# PanneauLed.net
KiCad netlist of a schematic drawn in Altium Designer
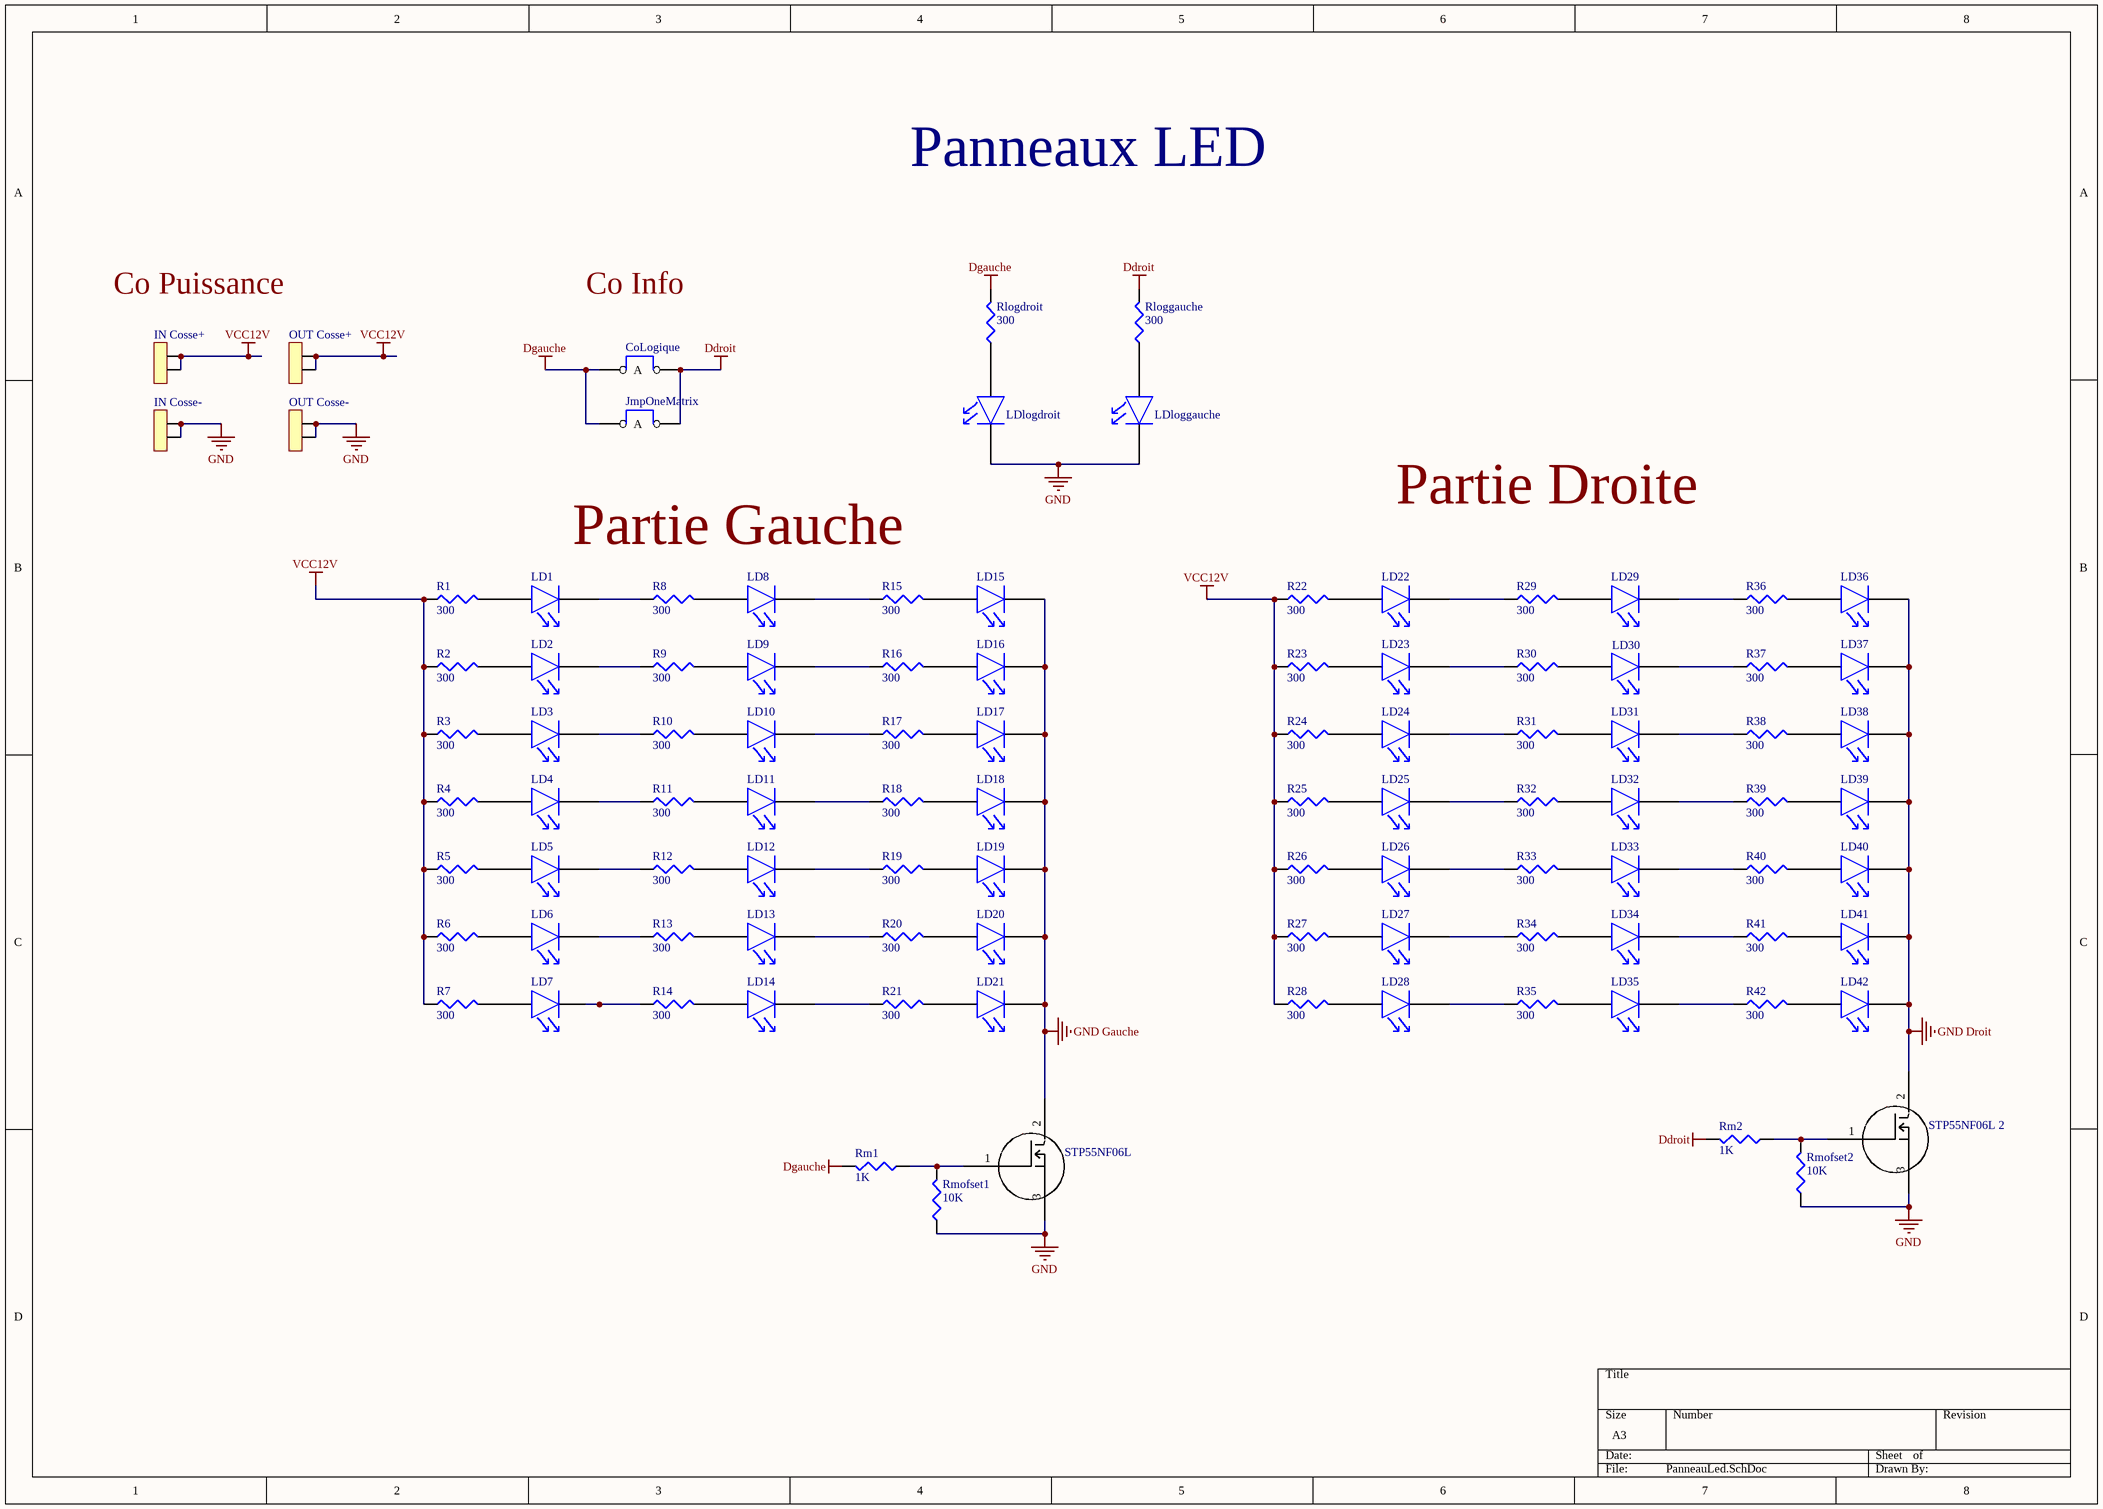
[diagram p0: PanneauLed.SchDoc]

(export (version "E")
  (design (tool "Eeschema 10.0.6"))
  (components
    (comp (ref "CoLogique")
      (value "JUMPER2")
      (footprint "JMP2-100")
      (description "cavalier 1 position")
      (libsource (lib "ISEN_basics") (part "JUMPER2"))
    )
    (comp (ref "IN Cosse+")
      (value "comment")
      (footprint "POWER2")
      (description "connecteur alim 2 pôles")
      (libsource (lib "ISEN_basics") (part "POWER2"))
    )
    (comp (ref "IN Cosse-")
      (value "comment")
      (footprint "POWER2")
      (description "connecteur alim 2 pôles")
      (libsource (lib "ISEN_basics") (part "POWER2"))
    )
    (comp (ref "JmpOneMatrix")
      (value "JUMPER2")
      (footprint "JMP2-100")
      (description "cavalier 1 position")
      (libsource (lib "ISEN_basics") (part "JUMPER2"))
    )
    (comp (ref "LD1")
      (value "comment")
      (footprint "LED1206")
      (description "LED 5mm/3mm/CMS")
      (libsource (lib "ISEN_basics") (part "LED"))
    )
    (comp (ref "LD2")
      (value "comment")
      (footprint "LED1206")
      (description "LED 5mm/3mm/CMS")
      (libsource (lib "ISEN_basics") (part "LED"))
    )
    (comp (ref "LD3")
      (value "comment")
      (footprint "LED1206")
      (description "LED 5mm/3mm/CMS")
      (libsource (lib "ISEN_basics") (part "LED"))
    )
    (comp (ref "LD4")
      (value "comment")
      (footprint "LED1206")
      (description "LED 5mm/3mm/CMS")
      (libsource (lib "ISEN_basics") (part "LED"))
    )
    (comp (ref "LD5")
      (value "comment")
      (footprint "LED1206")
      (description "LED 5mm/3mm/CMS")
      (libsource (lib "ISEN_basics") (part "LED"))
    )
    (comp (ref "LD6")
      (value "comment")
      (footprint "LED1206")
      (description "LED 5mm/3mm/CMS")
      (libsource (lib "ISEN_basics") (part "LED"))
    )
    (comp (ref "LD7")
      (value "comment")
      (footprint "LED1206")
      (description "LED 5mm/3mm/CMS")
      (libsource (lib "ISEN_basics") (part "LED"))
    )
    (comp (ref "LD8")
      (value "comment")
      (footprint "LED1206")
      (description "LED 5mm/3mm/CMS")
      (libsource (lib "ISEN_basics") (part "LED"))
    )
    (comp (ref "LD9")
      (value "comment")
      (footprint "LED1206")
      (description "LED 5mm/3mm/CMS")
      (libsource (lib "ISEN_basics") (part "LED"))
    )
    (comp (ref "LD10")
      (value "comment")
      (footprint "LED1206")
      (description "LED 5mm/3mm/CMS")
      (libsource (lib "ISEN_basics") (part "LED"))
    )
    (comp (ref "LD11")
      (value "comment")
      (footprint "LED1206")
      (description "LED 5mm/3mm/CMS")
      (libsource (lib "ISEN_basics") (part "LED"))
    )
    (comp (ref "LD12")
      (value "comment")
      (footprint "LED1206")
      (description "LED 5mm/3mm/CMS")
      (libsource (lib "ISEN_basics") (part "LED"))
    )
    (comp (ref "LD13")
      (value "comment")
      (footprint "LED1206")
      (description "LED 5mm/3mm/CMS")
      (libsource (lib "ISEN_basics") (part "LED"))
    )
    (comp (ref "LD14")
      (value "comment")
      (footprint "LED1206")
      (description "LED 5mm/3mm/CMS")
      (libsource (lib "ISEN_basics") (part "LED"))
    )
    (comp (ref "LD15")
      (value "comment")
      (footprint "LED1206")
      (description "LED 5mm/3mm/CMS")
      (libsource (lib "ISEN_basics") (part "LED"))
    )
    (comp (ref "LD16")
      (value "comment")
      (footprint "LED1206")
      (description "LED 5mm/3mm/CMS")
      (libsource (lib "ISEN_basics") (part "LED"))
    )
    (comp (ref "LD17")
      (value "comment")
      (footprint "LED1206")
      (description "LED 5mm/3mm/CMS")
      (libsource (lib "ISEN_basics") (part "LED"))
    )
    (comp (ref "LD18")
      (value "comment")
      (footprint "LED1206")
      (description "LED 5mm/3mm/CMS")
      (libsource (lib "ISEN_basics") (part "LED"))
    )
    (comp (ref "LD19")
      (value "comment")
      (footprint "LED1206")
      (description "LED 5mm/3mm/CMS")
      (libsource (lib "ISEN_basics") (part "LED"))
    )
    (comp (ref "LD20")
      (value "comment")
      (footprint "LED1206")
      (description "LED 5mm/3mm/CMS")
      (libsource (lib "ISEN_basics") (part "LED"))
    )
    (comp (ref "LD21")
      (value "comment")
      (footprint "LED1206")
      (description "LED 5mm/3mm/CMS")
      (libsource (lib "ISEN_basics") (part "LED"))
    )
    (comp (ref "LD22")
      (value "comment")
      (footprint "LED1206")
      (description "LED 5mm/3mm/CMS")
      (libsource (lib "ISEN_basics") (part "LED"))
    )
    (comp (ref "LD23")
      (value "comment")
      (footprint "LED1206")
      (description "LED 5mm/3mm/CMS")
      (libsource (lib "ISEN_basics") (part "LED"))
    )
    (comp (ref "LD24")
      (value "comment")
      (footprint "LED1206")
      (description "LED 5mm/3mm/CMS")
      (libsource (lib "ISEN_basics") (part "LED"))
    )
    (comp (ref "LD25")
      (value "comment")
      (footprint "LED1206")
      (description "LED 5mm/3mm/CMS")
      (libsource (lib "ISEN_basics") (part "LED"))
    )
    (comp (ref "LD26")
      (value "comment")
      (footprint "LED1206")
      (description "LED 5mm/3mm/CMS")
      (libsource (lib "ISEN_basics") (part "LED"))
    )
    (comp (ref "LD27")
      (value "comment")
      (footprint "LED1206")
      (description "LED 5mm/3mm/CMS")
      (libsource (lib "ISEN_basics") (part "LED"))
    )
    (comp (ref "LD28")
      (value "comment")
      (footprint "LED1206")
      (description "LED 5mm/3mm/CMS")
      (libsource (lib "ISEN_basics") (part "LED"))
    )
    (comp (ref "LD29")
      (value "comment")
      (footprint "LED1206")
      (description "LED 5mm/3mm/CMS")
      (libsource (lib "ISEN_basics") (part "LED"))
    )
    (comp (ref "LD30")
      (value "comment")
      (footprint "LED1206")
      (description "LED 5mm/3mm/CMS")
      (libsource (lib "ISEN_basics") (part "LED"))
    )
    (comp (ref "LD31")
      (value "comment")
      (footprint "LED1206")
      (description "LED 5mm/3mm/CMS")
      (libsource (lib "ISEN_basics") (part "LED"))
    )
    (comp (ref "LD32")
      (value "comment")
      (footprint "LED1206")
      (description "LED 5mm/3mm/CMS")
      (libsource (lib "ISEN_basics") (part "LED"))
    )
    (comp (ref "LD33")
      (value "comment")
      (footprint "LED1206")
      (description "LED 5mm/3mm/CMS")
      (libsource (lib "ISEN_basics") (part "LED"))
    )
    (comp (ref "LD34")
      (value "comment")
      (footprint "LED1206")
      (description "LED 5mm/3mm/CMS")
      (libsource (lib "ISEN_basics") (part "LED"))
    )
    (comp (ref "LD35")
      (value "comment")
      (footprint "LED1206")
      (description "LED 5mm/3mm/CMS")
      (libsource (lib "ISEN_basics") (part "LED"))
    )
    (comp (ref "LD36")
      (value "comment")
      (footprint "LED1206")
      (description "LED 5mm/3mm/CMS")
      (libsource (lib "ISEN_basics") (part "LED"))
    )
    (comp (ref "LD37")
      (value "comment")
      (footprint "LED1206")
      (description "LED 5mm/3mm/CMS")
      (libsource (lib "ISEN_basics") (part "LED"))
    )
    (comp (ref "LD38")
      (value "comment")
      (footprint "LED1206")
      (description "LED 5mm/3mm/CMS")
      (libsource (lib "ISEN_basics") (part "LED"))
    )
    (comp (ref "LD39")
      (value "comment")
      (footprint "LED1206")
      (description "LED 5mm/3mm/CMS")
      (libsource (lib "ISEN_basics") (part "LED"))
    )
    (comp (ref "LD40")
      (value "comment")
      (footprint "LED1206")
      (description "LED 5mm/3mm/CMS")
      (libsource (lib "ISEN_basics") (part "LED"))
    )
    (comp (ref "LD41")
      (value "comment")
      (footprint "LED1206")
      (description "LED 5mm/3mm/CMS")
      (libsource (lib "ISEN_basics") (part "LED"))
    )
    (comp (ref "LD42")
      (value "comment")
      (footprint "LED1206")
      (description "LED 5mm/3mm/CMS")
      (libsource (lib "ISEN_basics") (part "LED"))
    )
    (comp (ref "LDlogdroit")
      (value "comment")
      (footprint "LED1206")
      (description "LED 5mm/3mm/CMS")
      (libsource (lib "ISEN_basics") (part "LED"))
    )
    (comp (ref "LDloggauche")
      (value "comment")
      (footprint "LED1206")
      (description "LED 5mm/3mm/CMS")
      (libsource (lib "ISEN_basics") (part "LED"))
    )
    (comp (ref "OUT Cosse+")
      (value "~")
      (footprint "POWER2")
      (description "connecteur alim 2 pôles")
      (libsource (lib "ISEN_basics") (part "POWER2"))
    )
    (comp (ref "OUT Cosse-")
      (value "comment")
      (footprint "POWER2")
      (description "connecteur alim 2 pôles")
      (libsource (lib "ISEN_basics") (part "POWER2"))
    )
    (comp (ref "R1")
      (value "300")
      (footprint "0805")
      (description "resistance")
      (fields (field (name "Comment") "RES"))
      (libsource (lib "ISEN_basics") (part "RES"))
    )
    (comp (ref "R2")
      (value "300")
      (footprint "0805")
      (description "resistance")
      (fields (field (name "Comment") "RES"))
      (libsource (lib "ISEN_basics") (part "RES"))
    )
    (comp (ref "R3")
      (value "300")
      (footprint "0805")
      (description "resistance")
      (fields (field (name "Comment") "RES"))
      (libsource (lib "ISEN_basics") (part "RES"))
    )
    (comp (ref "R4")
      (value "300")
      (footprint "0805")
      (description "resistance")
      (fields (field (name "Comment") "RES"))
      (libsource (lib "ISEN_basics") (part "RES"))
    )
    (comp (ref "R5")
      (value "300")
      (footprint "0805")
      (description "resistance")
      (fields (field (name "Comment") "RES"))
      (libsource (lib "ISEN_basics") (part "RES"))
    )
    (comp (ref "R6")
      (value "300")
      (footprint "0805")
      (description "resistance")
      (fields (field (name "Comment") "RES"))
      (libsource (lib "ISEN_basics") (part "RES"))
    )
    (comp (ref "R7")
      (value "300")
      (footprint "0805")
      (description "resistance")
      (fields (field (name "Comment") "RES"))
      (libsource (lib "ISEN_basics") (part "RES"))
    )
    (comp (ref "R8")
      (value "300")
      (footprint "0805")
      (description "resistance")
      (fields (field (name "Comment") "RES"))
      (libsource (lib "ISEN_basics") (part "RES"))
    )
    (comp (ref "R9")
      (value "300")
      (footprint "0805")
      (description "resistance")
      (fields (field (name "Comment") "RES"))
      (libsource (lib "ISEN_basics") (part "RES"))
    )
    (comp (ref "R10")
      (value "300")
      (footprint "0805")
      (description "resistance")
      (fields (field (name "Comment") "RES"))
      (libsource (lib "ISEN_basics") (part "RES"))
    )
    (comp (ref "R11")
      (value "300")
      (footprint "0805")
      (description "resistance")
      (fields (field (name "Comment") "RES"))
      (libsource (lib "ISEN_basics") (part "RES"))
    )
    (comp (ref "R12")
      (value "300")
      (footprint "0805")
      (description "resistance")
      (fields (field (name "Comment") "RES"))
      (libsource (lib "ISEN_basics") (part "RES"))
    )
    (comp (ref "R13")
      (value "300")
      (footprint "0805")
      (description "resistance")
      (fields (field (name "Comment") "RES"))
      (libsource (lib "ISEN_basics") (part "RES"))
    )
    (comp (ref "R14")
      (value "300")
      (footprint "0805")
      (description "resistance")
      (fields (field (name "Comment") "RES"))
      (libsource (lib "ISEN_basics") (part "RES"))
    )
    (comp (ref "R15")
      (value "300")
      (footprint "0805")
      (description "resistance")
      (fields (field (name "Comment") "RES"))
      (libsource (lib "ISEN_basics") (part "RES"))
    )
    (comp (ref "R16")
      (value "300")
      (footprint "0805")
      (description "resistance")
      (fields (field (name "Comment") "RES"))
      (libsource (lib "ISEN_basics") (part "RES"))
    )
    (comp (ref "R17")
      (value "300")
      (footprint "0805")
      (description "resistance")
      (fields (field (name "Comment") "RES"))
      (libsource (lib "ISEN_basics") (part "RES"))
    )
    (comp (ref "R18")
      (value "300")
      (footprint "0805")
      (description "resistance")
      (fields (field (name "Comment") "RES"))
      (libsource (lib "ISEN_basics") (part "RES"))
    )
    (comp (ref "R19")
      (value "300")
      (footprint "0805")
      (description "resistance")
      (fields (field (name "Comment") "RES"))
      (libsource (lib "ISEN_basics") (part "RES"))
    )
    (comp (ref "R20")
      (value "300")
      (footprint "0805")
      (description "resistance")
      (fields (field (name "Comment") "RES"))
      (libsource (lib "ISEN_basics") (part "RES"))
    )
    (comp (ref "R21")
      (value "300")
      (footprint "0805")
      (description "resistance")
      (fields (field (name "Comment") "RES"))
      (libsource (lib "ISEN_basics") (part "RES"))
    )
    (comp (ref "R22")
      (value "300")
      (footprint "0805")
      (description "resistance")
      (fields (field (name "Comment") "RES"))
      (libsource (lib "ISEN_basics") (part "RES"))
    )
    (comp (ref "R23")
      (value "300")
      (footprint "0805")
      (description "resistance")
      (fields (field (name "Comment") "RES"))
      (libsource (lib "ISEN_basics") (part "RES"))
    )
    (comp (ref "R24")
      (value "300")
      (footprint "0805")
      (description "resistance")
      (fields (field (name "Comment") "RES"))
      (libsource (lib "ISEN_basics") (part "RES"))
    )
    (comp (ref "R25")
      (value "300")
      (footprint "0805")
      (description "resistance")
      (fields (field (name "Comment") "RES"))
      (libsource (lib "ISEN_basics") (part "RES"))
    )
    (comp (ref "R26")
      (value "300")
      (footprint "0805")
      (description "resistance")
      (fields (field (name "Comment") "RES"))
      (libsource (lib "ISEN_basics") (part "RES"))
    )
    (comp (ref "R27")
      (value "300")
      (footprint "0805")
      (description "resistance")
      (fields (field (name "Comment") "RES"))
      (libsource (lib "ISEN_basics") (part "RES"))
    )
    (comp (ref "R28")
      (value "300")
      (footprint "0805")
      (description "resistance")
      (fields (field (name "Comment") "RES"))
      (libsource (lib "ISEN_basics") (part "RES"))
    )
    (comp (ref "R29")
      (value "300")
      (footprint "0805")
      (description "resistance")
      (fields (field (name "Comment") "RES"))
      (libsource (lib "ISEN_basics") (part "RES"))
    )
    (comp (ref "R30")
      (value "300")
      (footprint "0805")
      (description "resistance")
      (fields (field (name "Comment") "RES"))
      (libsource (lib "ISEN_basics") (part "RES"))
    )
    (comp (ref "R31")
      (value "300")
      (footprint "0805")
      (description "resistance")
      (fields (field (name "Comment") "RES"))
      (libsource (lib "ISEN_basics") (part "RES"))
    )
    (comp (ref "R32")
      (value "300")
      (footprint "0805")
      (description "resistance")
      (fields (field (name "Comment") "RES"))
      (libsource (lib "ISEN_basics") (part "RES"))
    )
    (comp (ref "R33")
      (value "300")
      (footprint "0805")
      (description "resistance")
      (fields (field (name "Comment") "RES"))
      (libsource (lib "ISEN_basics") (part "RES"))
    )
    (comp (ref "R34")
      (value "300")
      (footprint "0805")
      (description "resistance")
      (fields (field (name "Comment") "RES"))
      (libsource (lib "ISEN_basics") (part "RES"))
    )
    (comp (ref "R35")
      (value "300")
      (footprint "0805")
      (description "resistance")
      (fields (field (name "Comment") "RES"))
      (libsource (lib "ISEN_basics") (part "RES"))
    )
    (comp (ref "R36")
      (value "300")
      (footprint "0805")
      (description "resistance")
      (fields (field (name "Comment") "RES"))
      (libsource (lib "ISEN_basics") (part "RES"))
    )
    (comp (ref "R37")
      (value "300")
      (footprint "0805")
      (description "resistance")
      (fields (field (name "Comment") "RES"))
      (libsource (lib "ISEN_basics") (part "RES"))
    )
    (comp (ref "R38")
      (value "300")
      (footprint "0805")
      (description "resistance")
      (fields (field (name "Comment") "RES"))
      (libsource (lib "ISEN_basics") (part "RES"))
    )
    (comp (ref "R39")
      (value "300")
      (footprint "0805")
      (description "resistance")
      (fields (field (name "Comment") "RES"))
      (libsource (lib "ISEN_basics") (part "RES"))
    )
    (comp (ref "R40")
      (value "300")
      (footprint "0805")
      (description "resistance")
      (fields (field (name "Comment") "RES"))
      (libsource (lib "ISEN_basics") (part "RES"))
    )
    (comp (ref "R41")
      (value "300")
      (footprint "0805")
      (description "resistance")
      (fields (field (name "Comment") "RES"))
      (libsource (lib "ISEN_basics") (part "RES"))
    )
    (comp (ref "R42")
      (value "300")
      (footprint "0805")
      (description "resistance")
      (fields (field (name "Comment") "RES"))
      (libsource (lib "ISEN_basics") (part "RES"))
    )
    (comp (ref "Rlogdroit")
      (value "300")
      (footprint "0805")
      (description "resistance")
      (fields (field (name "Comment") "RES"))
      (libsource (lib "ISEN_basics") (part "RES"))
    )
    (comp (ref "Rloggauche")
      (value "300")
      (footprint "0805")
      (description "resistance")
      (fields (field (name "Comment") "RES"))
      (libsource (lib "ISEN_basics") (part "RES"))
    )
    (comp (ref "Rm1")
      (value "1K")
      (footprint "0805")
      (description "resistance")
      (fields (field (name "Comment") "RES"))
      (libsource (lib "ISEN_basics") (part "RES"))
    )
    (comp (ref "Rm2")
      (value "1K")
      (footprint "0805")
      (description "resistance")
      (fields (field (name "Comment") "RES"))
      (libsource (lib "ISEN_basics") (part "RES"))
    )
    (comp (ref "Rmofset1")
      (value "10K")
      (footprint "0805")
      (description "resistance")
      (fields (field (name "Comment") "RES"))
      (libsource (lib "ISEN_basics") (part "RES"))
    )
    (comp (ref "Rmofset2")
      (value "10K")
      (footprint "0805")
      (description "resistance")
      (fields (field (name "Comment") "RES"))
      (libsource (lib "ISEN_basics") (part "RES"))
    )
    (comp (ref "STP55NF06L")
      (value "STP55NF06L")
      (footprint "STP55NF06L")
      (libsource (lib "Mofset") (part "STP55NF06L"))
    )
    (comp (ref "STP55NF06L 2")
      (value "STP55NF06L")
      (footprint "STP55NF06L")
      (libsource (lib "Mofset") (part "STP55NF06L"))
    )
  )
  (nets
    (net (code "1") (name "Ddroit") (class "Default")
      (node (ref "CoLogique") (pin "2") (pinfunction "com_2") (pintype "passive"))
      (node (ref "JmpOneMatrix") (pin "2") (pinfunction "com_2") (pintype "passive"))
      (node (ref "Rloggauche") (pin "2") (pintype "passive"))
      (node (ref "Rm2") (pin "2") (pintype "passive"))
    )
    (net (code "2") (name "Dgauche") (class "Default")
      (node (ref "CoLogique") (pin "1") (pinfunction "A_1") (pintype "passive"))
      (node (ref "JmpOneMatrix") (pin "1") (pinfunction "A_1") (pintype "passive"))
      (node (ref "Rlogdroit") (pin "2") (pintype "passive"))
      (node (ref "Rm1") (pin "2") (pintype "passive"))
    )
    (net (code "3") (name "GND") (class "Default")
      (node (ref "IN Cosse-") (pin "1") (pintype "passive"))
      (node (ref "IN Cosse-") (pin "2") (pintype "passive"))
      (node (ref "LDlogdroit") (pin "K") (pinfunction "10_K") (pintype "passive"))
      (node (ref "LDloggauche") (pin "K") (pinfunction "10_K") (pintype "passive"))
      (node (ref "OUT Cosse-") (pin "1") (pintype "passive"))
      (node (ref "OUT Cosse-") (pin "2") (pintype "passive"))
      (node (ref "Rmofset1") (pin "1") (pintype "passive"))
      (node (ref "Rmofset2") (pin "1") (pintype "passive"))
      (node (ref "STP55NF06L") (pin "3") (pinfunction "3_3") (pintype "passive"))
      (node (ref "STP55NF06L 2") (pin "3") (pinfunction "3_3") (pintype "passive"))
    )
    (net (code "4") (name "GND Droit") (class "Default")
      (node (ref "LD36") (pin "K") (pinfunction "10_K") (pintype "passive"))
      (node (ref "LD37") (pin "K") (pinfunction "10_K") (pintype "passive"))
      (node (ref "LD38") (pin "K") (pinfunction "10_K") (pintype "passive"))
      (node (ref "LD39") (pin "K") (pinfunction "10_K") (pintype "passive"))
      (node (ref "LD40") (pin "K") (pinfunction "10_K") (pintype "passive"))
      (node (ref "LD41") (pin "K") (pinfunction "10_K") (pintype "passive"))
      (node (ref "LD42") (pin "K") (pinfunction "10_K") (pintype "passive"))
      (node (ref "STP55NF06L 2") (pin "2") (pinfunction "2_2") (pintype "passive"))
    )
    (net (code "5") (name "GND Gauche") (class "Default")
      (node (ref "LD15") (pin "K") (pinfunction "10_K") (pintype "passive"))
      (node (ref "LD16") (pin "K") (pinfunction "10_K") (pintype "passive"))
      (node (ref "LD17") (pin "K") (pinfunction "10_K") (pintype "passive"))
      (node (ref "LD18") (pin "K") (pinfunction "10_K") (pintype "passive"))
      (node (ref "LD19") (pin "K") (pinfunction "10_K") (pintype "passive"))
      (node (ref "LD20") (pin "K") (pinfunction "10_K") (pintype "passive"))
      (node (ref "LD21") (pin "K") (pinfunction "10_K") (pintype "passive"))
      (node (ref "STP55NF06L") (pin "2") (pinfunction "2_2") (pintype "passive"))
    )
    (net (code "6") (name "Net-(LD1-8)") (class "Default")
      (node (ref "LD1") (pin "A") (pinfunction "8_A") (pintype "passive"))
      (node (ref "R1") (pin "2") (pintype "passive"))
    )
    (net (code "7") (name "Net-(LD1-10)") (class "Default")
      (node (ref "LD1") (pin "K") (pinfunction "10_K") (pintype "passive"))
      (node (ref "R8") (pin "1") (pintype "passive"))
    )
    (net (code "8") (name "Net-(LD2-8)") (class "Default")
      (node (ref "LD2") (pin "A") (pinfunction "8_A") (pintype "passive"))
      (node (ref "R2") (pin "2") (pintype "passive"))
    )
    (net (code "9") (name "Net-(LD2-10)") (class "Default")
      (node (ref "LD2") (pin "K") (pinfunction "10_K") (pintype "passive"))
      (node (ref "R9") (pin "1") (pintype "passive"))
    )
    (net (code "10") (name "Net-(LD3-8)") (class "Default")
      (node (ref "LD3") (pin "A") (pinfunction "8_A") (pintype "passive"))
      (node (ref "R3") (pin "2") (pintype "passive"))
    )
    (net (code "11") (name "Net-(LD3-10)") (class "Default")
      (node (ref "LD3") (pin "K") (pinfunction "10_K") (pintype "passive"))
      (node (ref "R10") (pin "1") (pintype "passive"))
    )
    (net (code "12") (name "Net-(LD4-8)") (class "Default")
      (node (ref "LD4") (pin "A") (pinfunction "8_A") (pintype "passive"))
      (node (ref "R4") (pin "2") (pintype "passive"))
    )
    (net (code "13") (name "Net-(LD4-10)") (class "Default")
      (node (ref "LD4") (pin "K") (pinfunction "10_K") (pintype "passive"))
      (node (ref "R11") (pin "1") (pintype "passive"))
    )
    (net (code "14") (name "Net-(LD5-8)") (class "Default")
      (node (ref "LD5") (pin "A") (pinfunction "8_A") (pintype "passive"))
      (node (ref "R5") (pin "2") (pintype "passive"))
    )
    (net (code "15") (name "Net-(LD5-10)") (class "Default")
      (node (ref "LD5") (pin "K") (pinfunction "10_K") (pintype "passive"))
      (node (ref "R12") (pin "1") (pintype "passive"))
    )
    (net (code "16") (name "Net-(LD6-8)") (class "Default")
      (node (ref "LD6") (pin "A") (pinfunction "8_A") (pintype "passive"))
      (node (ref "R6") (pin "2") (pintype "passive"))
    )
    (net (code "17") (name "Net-(LD6-10)") (class "Default")
      (node (ref "LD6") (pin "K") (pinfunction "10_K") (pintype "passive"))
      (node (ref "R13") (pin "1") (pintype "passive"))
    )
    (net (code "18") (name "Net-(LD7-8)") (class "Default")
      (node (ref "LD7") (pin "A") (pinfunction "8_A") (pintype "passive"))
      (node (ref "R7") (pin "2") (pintype "passive"))
    )
    (net (code "19") (name "Net-(LD7-10)") (class "Default")
      (node (ref "LD7") (pin "K") (pinfunction "10_K") (pintype "passive"))
      (node (ref "R14") (pin "1") (pintype "passive"))
    )
    (net (code "20") (name "Net-(LD8-8)") (class "Default")
      (node (ref "LD8") (pin "A") (pinfunction "8_A") (pintype "passive"))
      (node (ref "R8") (pin "2") (pintype "passive"))
    )
    (net (code "21") (name "Net-(LD8-10)") (class "Default")
      (node (ref "LD8") (pin "K") (pinfunction "10_K") (pintype "passive"))
      (node (ref "R15") (pin "1") (pintype "passive"))
    )
    (net (code "22") (name "Net-(LD9-8)") (class "Default")
      (node (ref "LD9") (pin "A") (pinfunction "8_A") (pintype "passive"))
      (node (ref "R9") (pin "2") (pintype "passive"))
    )
    (net (code "23") (name "Net-(LD9-10)") (class "Default")
      (node (ref "LD9") (pin "K") (pinfunction "10_K") (pintype "passive"))
      (node (ref "R16") (pin "1") (pintype "passive"))
    )
    (net (code "24") (name "Net-(LD10-8)") (class "Default")
      (node (ref "LD10") (pin "A") (pinfunction "8_A") (pintype "passive"))
      (node (ref "R10") (pin "2") (pintype "passive"))
    )
    (net (code "25") (name "Net-(LD10-10)") (class "Default")
      (node (ref "LD10") (pin "K") (pinfunction "10_K") (pintype "passive"))
      (node (ref "R17") (pin "1") (pintype "passive"))
    )
    (net (code "26") (name "Net-(LD11-8)") (class "Default")
      (node (ref "LD11") (pin "A") (pinfunction "8_A") (pintype "passive"))
      (node (ref "R11") (pin "2") (pintype "passive"))
    )
    (net (code "27") (name "Net-(LD11-10)") (class "Default")
      (node (ref "LD11") (pin "K") (pinfunction "10_K") (pintype "passive"))
      (node (ref "R18") (pin "1") (pintype "passive"))
    )
    (net (code "28") (name "Net-(LD12-8)") (class "Default")
      (node (ref "LD12") (pin "A") (pinfunction "8_A") (pintype "passive"))
      (node (ref "R12") (pin "2") (pintype "passive"))
    )
    (net (code "29") (name "Net-(LD12-10)") (class "Default")
      (node (ref "LD12") (pin "K") (pinfunction "10_K") (pintype "passive"))
      (node (ref "R19") (pin "1") (pintype "passive"))
    )
    (net (code "30") (name "Net-(LD13-8)") (class "Default")
      (node (ref "LD13") (pin "A") (pinfunction "8_A") (pintype "passive"))
      (node (ref "R13") (pin "2") (pintype "passive"))
    )
    (net (code "31") (name "Net-(LD13-10)") (class "Default")
      (node (ref "LD13") (pin "K") (pinfunction "10_K") (pintype "passive"))
      (node (ref "R20") (pin "1") (pintype "passive"))
    )
    (net (code "32") (name "Net-(LD14-8)") (class "Default")
      (node (ref "LD14") (pin "A") (pinfunction "8_A") (pintype "passive"))
      (node (ref "R14") (pin "2") (pintype "passive"))
    )
    (net (code "33") (name "Net-(LD14-10)") (class "Default")
      (node (ref "LD14") (pin "K") (pinfunction "10_K") (pintype "passive"))
      (node (ref "R21") (pin "1") (pintype "passive"))
    )
    (net (code "34") (name "Net-(LD15-8)") (class "Default")
      (node (ref "LD15") (pin "A") (pinfunction "8_A") (pintype "passive"))
      (node (ref "R15") (pin "2") (pintype "passive"))
    )
    (net (code "35") (name "Net-(LD16-8)") (class "Default")
      (node (ref "LD16") (pin "A") (pinfunction "8_A") (pintype "passive"))
      (node (ref "R16") (pin "2") (pintype "passive"))
    )
    (net (code "36") (name "Net-(LD17-8)") (class "Default")
      (node (ref "LD17") (pin "A") (pinfunction "8_A") (pintype "passive"))
      (node (ref "R17") (pin "2") (pintype "passive"))
    )
    (net (code "37") (name "Net-(LD18-8)") (class "Default")
      (node (ref "LD18") (pin "A") (pinfunction "8_A") (pintype "passive"))
      (node (ref "R18") (pin "2") (pintype "passive"))
    )
    (net (code "38") (name "Net-(LD19-8)") (class "Default")
      (node (ref "LD19") (pin "A") (pinfunction "8_A") (pintype "passive"))
      (node (ref "R19") (pin "2") (pintype "passive"))
    )
    (net (code "39") (name "Net-(LD20-8)") (class "Default")
      (node (ref "LD20") (pin "A") (pinfunction "8_A") (pintype "passive"))
      (node (ref "R20") (pin "2") (pintype "passive"))
    )
    (net (code "40") (name "Net-(LD21-8)") (class "Default")
      (node (ref "LD21") (pin "A") (pinfunction "8_A") (pintype "passive"))
      (node (ref "R21") (pin "2") (pintype "passive"))
    )
    (net (code "41") (name "Net-(LD22-8)") (class "Default")
      (node (ref "LD22") (pin "A") (pinfunction "8_A") (pintype "passive"))
      (node (ref "R22") (pin "2") (pintype "passive"))
    )
    (net (code "42") (name "Net-(LD22-10)") (class "Default")
      (node (ref "LD22") (pin "K") (pinfunction "10_K") (pintype "passive"))
      (node (ref "R29") (pin "1") (pintype "passive"))
    )
    (net (code "43") (name "Net-(LD23-8)") (class "Default")
      (node (ref "LD23") (pin "A") (pinfunction "8_A") (pintype "passive"))
      (node (ref "R23") (pin "2") (pintype "passive"))
    )
    (net (code "44") (name "Net-(LD23-10)") (class "Default")
      (node (ref "LD23") (pin "K") (pinfunction "10_K") (pintype "passive"))
      (node (ref "R30") (pin "1") (pintype "passive"))
    )
    (net (code "45") (name "Net-(LD24-8)") (class "Default")
      (node (ref "LD24") (pin "A") (pinfunction "8_A") (pintype "passive"))
      (node (ref "R24") (pin "2") (pintype "passive"))
    )
    (net (code "46") (name "Net-(LD24-10)") (class "Default")
      (node (ref "LD24") (pin "K") (pinfunction "10_K") (pintype "passive"))
      (node (ref "R31") (pin "1") (pintype "passive"))
    )
    (net (code "47") (name "Net-(LD25-8)") (class "Default")
      (node (ref "LD25") (pin "A") (pinfunction "8_A") (pintype "passive"))
      (node (ref "R25") (pin "2") (pintype "passive"))
    )
    (net (code "48") (name "Net-(LD25-10)") (class "Default")
      (node (ref "LD25") (pin "K") (pinfunction "10_K") (pintype "passive"))
      (node (ref "R32") (pin "1") (pintype "passive"))
    )
    (net (code "49") (name "Net-(LD26-8)") (class "Default")
      (node (ref "LD26") (pin "A") (pinfunction "8_A") (pintype "passive"))
      (node (ref "R26") (pin "2") (pintype "passive"))
    )
    (net (code "50") (name "Net-(LD26-10)") (class "Default")
      (node (ref "LD26") (pin "K") (pinfunction "10_K") (pintype "passive"))
      (node (ref "R33") (pin "1") (pintype "passive"))
    )
    (net (code "51") (name "Net-(LD27-8)") (class "Default")
      (node (ref "LD27") (pin "A") (pinfunction "8_A") (pintype "passive"))
      (node (ref "R27") (pin "2") (pintype "passive"))
    )
    (net (code "52") (name "Net-(LD27-10)") (class "Default")
      (node (ref "LD27") (pin "K") (pinfunction "10_K") (pintype "passive"))
      (node (ref "R34") (pin "1") (pintype "passive"))
    )
    (net (code "53") (name "Net-(LD28-8)") (class "Default")
      (node (ref "LD28") (pin "A") (pinfunction "8_A") (pintype "passive"))
      (node (ref "R28") (pin "2") (pintype "passive"))
    )
    (net (code "54") (name "Net-(LD28-10)") (class "Default")
      (node (ref "LD28") (pin "K") (pinfunction "10_K") (pintype "passive"))
      (node (ref "R35") (pin "1") (pintype "passive"))
    )
    (net (code "55") (name "Net-(LD29-8)") (class "Default")
      (node (ref "LD29") (pin "A") (pinfunction "8_A") (pintype "passive"))
      (node (ref "R29") (pin "2") (pintype "passive"))
    )
    (net (code "56") (name "Net-(LD29-10)") (class "Default")
      (node (ref "LD29") (pin "K") (pinfunction "10_K") (pintype "passive"))
      (node (ref "R36") (pin "1") (pintype "passive"))
    )
    (net (code "57") (name "Net-(LD30-8)") (class "Default")
      (node (ref "LD30") (pin "A") (pinfunction "8_A") (pintype "passive"))
      (node (ref "R30") (pin "2") (pintype "passive"))
    )
    (net (code "58") (name "Net-(LD30-10)") (class "Default")
      (node (ref "LD30") (pin "K") (pinfunction "10_K") (pintype "passive"))
      (node (ref "R37") (pin "1") (pintype "passive"))
    )
    (net (code "59") (name "Net-(LD31-8)") (class "Default")
      (node (ref "LD31") (pin "A") (pinfunction "8_A") (pintype "passive"))
      (node (ref "R31") (pin "2") (pintype "passive"))
    )
    (net (code "60") (name "Net-(LD31-10)") (class "Default")
      (node (ref "LD31") (pin "K") (pinfunction "10_K") (pintype "passive"))
      (node (ref "R38") (pin "1") (pintype "passive"))
    )
    (net (code "61") (name "Net-(LD32-8)") (class "Default")
      (node (ref "LD32") (pin "A") (pinfunction "8_A") (pintype "passive"))
      (node (ref "R32") (pin "2") (pintype "passive"))
    )
    (net (code "62") (name "Net-(LD32-10)") (class "Default")
      (node (ref "LD32") (pin "K") (pinfunction "10_K") (pintype "passive"))
      (node (ref "R39") (pin "1") (pintype "passive"))
    )
    (net (code "63") (name "Net-(LD33-8)") (class "Default")
      (node (ref "LD33") (pin "A") (pinfunction "8_A") (pintype "passive"))
      (node (ref "R33") (pin "2") (pintype "passive"))
    )
    (net (code "64") (name "Net-(LD33-10)") (class "Default")
      (node (ref "LD33") (pin "K") (pinfunction "10_K") (pintype "passive"))
      (node (ref "R40") (pin "1") (pintype "passive"))
    )
    (net (code "65") (name "Net-(LD34-8)") (class "Default")
      (node (ref "LD34") (pin "A") (pinfunction "8_A") (pintype "passive"))
      (node (ref "R34") (pin "2") (pintype "passive"))
    )
    (net (code "66") (name "Net-(LD34-10)") (class "Default")
      (node (ref "LD34") (pin "K") (pinfunction "10_K") (pintype "passive"))
      (node (ref "R41") (pin "1") (pintype "passive"))
    )
    (net (code "67") (name "Net-(LD35-8)") (class "Default")
      (node (ref "LD35") (pin "A") (pinfunction "8_A") (pintype "passive"))
      (node (ref "R35") (pin "2") (pintype "passive"))
    )
    (net (code "68") (name "Net-(LD35-10)") (class "Default")
      (node (ref "LD35") (pin "K") (pinfunction "10_K") (pintype "passive"))
      (node (ref "R42") (pin "1") (pintype "passive"))
    )
    (net (code "69") (name "Net-(LD36-8)") (class "Default")
      (node (ref "LD36") (pin "A") (pinfunction "8_A") (pintype "passive"))
      (node (ref "R36") (pin "2") (pintype "passive"))
    )
    (net (code "70") (name "Net-(LD37-8)") (class "Default")
      (node (ref "LD37") (pin "A") (pinfunction "8_A") (pintype "passive"))
      (node (ref "R37") (pin "2") (pintype "passive"))
    )
    (net (code "71") (name "Net-(LD38-8)") (class "Default")
      (node (ref "LD38") (pin "A") (pinfunction "8_A") (pintype "passive"))
      (node (ref "R38") (pin "2") (pintype "passive"))
    )
    (net (code "72") (name "Net-(LD39-8)") (class "Default")
      (node (ref "LD39") (pin "A") (pinfunction "8_A") (pintype "passive"))
      (node (ref "R39") (pin "2") (pintype "passive"))
    )
    (net (code "73") (name "Net-(LD40-8)") (class "Default")
      (node (ref "LD40") (pin "A") (pinfunction "8_A") (pintype "passive"))
      (node (ref "R40") (pin "2") (pintype "passive"))
    )
    (net (code "74") (name "Net-(LD41-8)") (class "Default")
      (node (ref "LD41") (pin "A") (pinfunction "8_A") (pintype "passive"))
      (node (ref "R41") (pin "2") (pintype "passive"))
    )
    (net (code "75") (name "Net-(LD42-8)") (class "Default")
      (node (ref "LD42") (pin "A") (pinfunction "8_A") (pintype "passive"))
      (node (ref "R42") (pin "2") (pintype "passive"))
    )
    (net (code "76") (name "Net-(LDlogdroit-8)") (class "Default")
      (node (ref "LDlogdroit") (pin "A") (pinfunction "8_A") (pintype "passive"))
      (node (ref "Rlogdroit") (pin "1") (pintype "passive"))
    )
    (net (code "77") (name "Net-(LDloggauche-8)") (class "Default")
      (node (ref "LDloggauche") (pin "A") (pinfunction "8_A") (pintype "passive"))
      (node (ref "Rloggauche") (pin "1") (pintype "passive"))
    )
    (net (code "78") (name "Net-(Rm1-Pad1)") (class "Default")
      (node (ref "Rm1") (pin "1") (pintype "passive"))
      (node (ref "Rmofset1") (pin "2") (pintype "passive"))
      (node (ref "STP55NF06L") (pin "1") (pinfunction "1_1") (pintype "passive"))
    )
    (net (code "79") (name "Net-(Rm2-Pad1)") (class "Default")
      (node (ref "Rm2") (pin "1") (pintype "passive"))
      (node (ref "Rmofset2") (pin "2") (pintype "passive"))
      (node (ref "STP55NF06L 2") (pin "1") (pinfunction "1_1") (pintype "passive"))
    )
    (net (code "80") (name "VCC12V") (class "Default")
      (node (ref "IN Cosse+") (pin "1") (pintype "passive"))
      (node (ref "IN Cosse+") (pin "2") (pintype "passive"))
      (node (ref "OUT Cosse+") (pin "1") (pintype "passive"))
      (node (ref "OUT Cosse+") (pin "2") (pintype "passive"))
      (node (ref "R1") (pin "1") (pintype "passive"))
      (node (ref "R2") (pin "1") (pintype "passive"))
      (node (ref "R22") (pin "1") (pintype "passive"))
      (node (ref "R23") (pin "1") (pintype "passive"))
      (node (ref "R24") (pin "1") (pintype "passive"))
      (node (ref "R25") (pin "1") (pintype "passive"))
      (node (ref "R26") (pin "1") (pintype "passive"))
      (node (ref "R27") (pin "1") (pintype "passive"))
      (node (ref "R28") (pin "1") (pintype "passive"))
      (node (ref "R3") (pin "1") (pintype "passive"))
      (node (ref "R4") (pin "1") (pintype "passive"))
      (node (ref "R5") (pin "1") (pintype "passive"))
      (node (ref "R6") (pin "1") (pintype "passive"))
      (node (ref "R7") (pin "1") (pintype "passive"))
    )
  )
)
